# SCH_schematicdesign_2025-10-19.net
KiCad netlist of a schematic drawn in EasyEDA
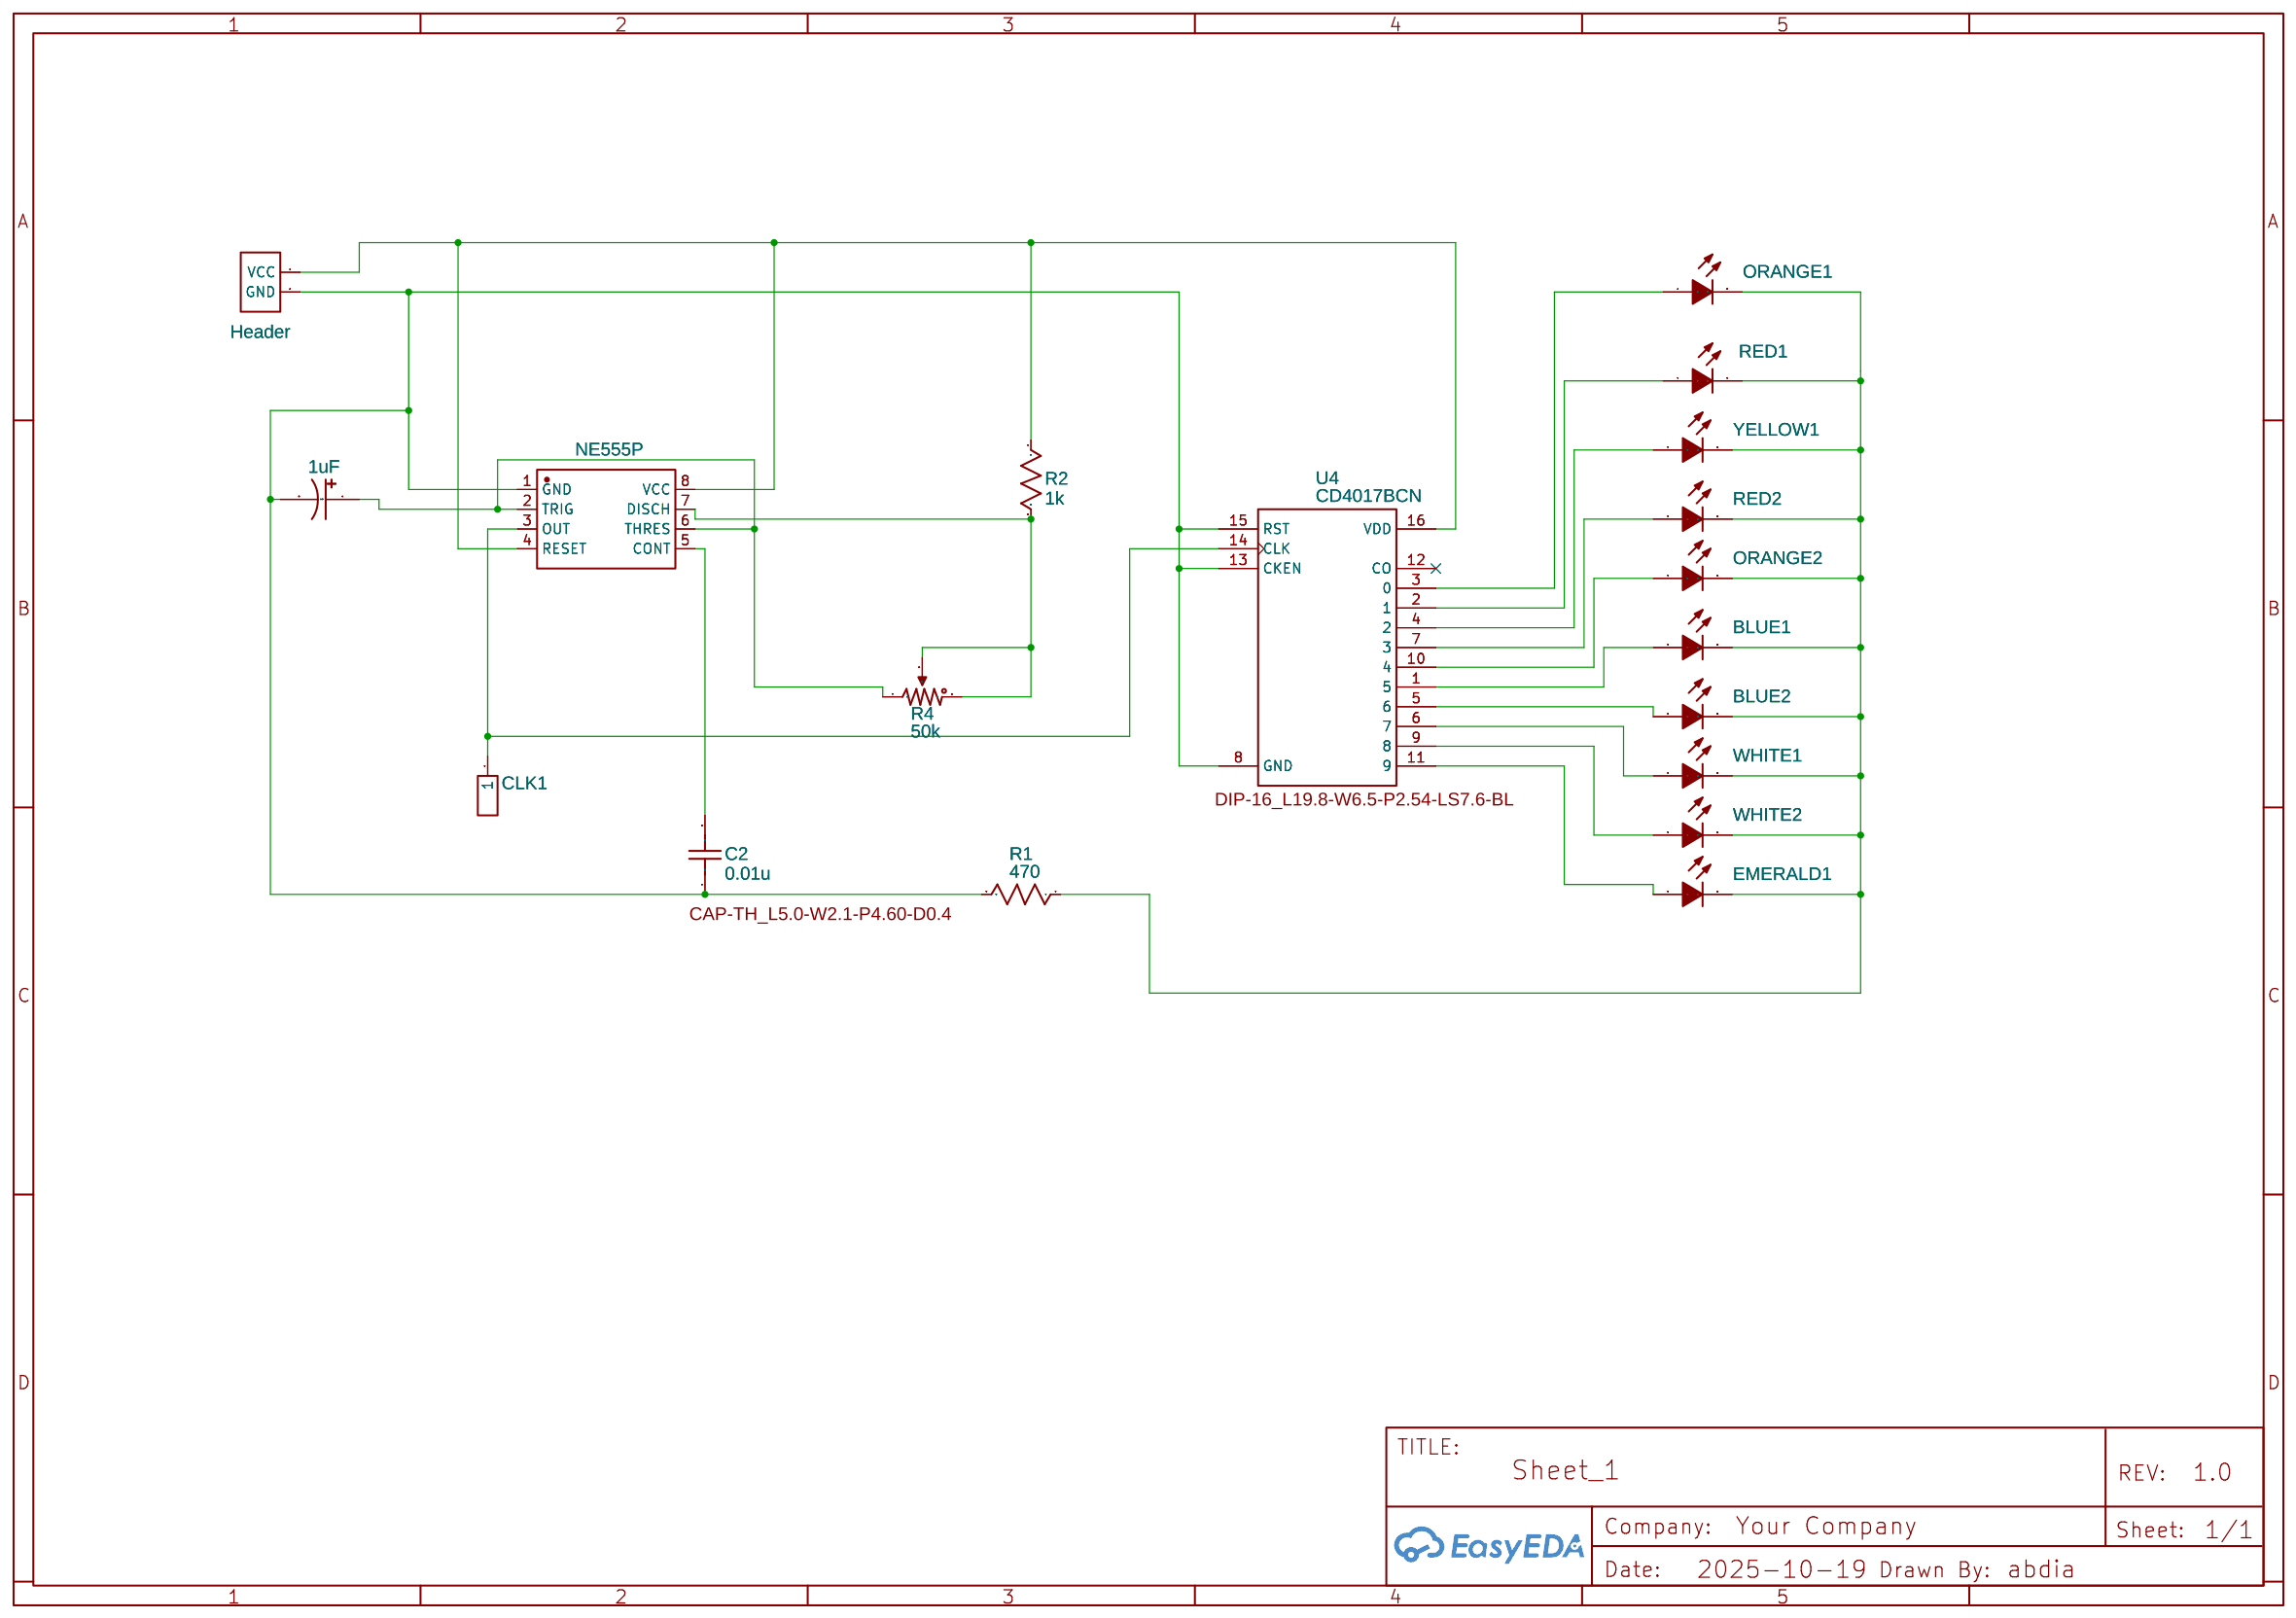
[diagram p0: schematic sheet]

(export (version "E")
  (design (tool "Eeschema 10.0.6"))
  (components
    (comp (ref "BLUE1") (value "LED_5MM") (libsource (lib "") (part "LED_5MM_2")))
    (comp (ref "BLUE2") (value "LED_5MM") (libsource (lib "") (part "LED_5MM_2")))
    (comp (ref "C1")
      (value "1uF")
      (fields (field (name "Manufacturer Part") "UVZ1H010MDD") (field (name "Manufacturer") "Nichicon(尼吉康)"))
      (libsource (lib "") (part "UVZ1H010MDD"))
    )
    (comp (ref "C2") (value "0.01u") (libsource (lib "") (part "C_0603_US")))
    (comp (ref "CLK1")
      (value "C81276")
      (fields
        (field (name "Manufacturer Part") "2.54-1*1P针")
        (field (name "Manufacturer") "BOOMELE(Boom Precision Elec)")
      )
      (libsource (lib "") (part "Header-Male-2.54_1x1"))
    )
    (comp (ref "EMERALD1") (value "LED_5MM") (libsource (lib "") (part "LED_5MM_5")))
    (comp (ref "H1") (value "Header") (libsource (lib "") (part "HEADER-FEMALE-2.54_1X2")))
    (comp (ref "ORANGE1") (value "LED_5MM") (libsource (lib "") (part "LED_5MM_3")))
    (comp (ref "ORANGE2") (value "LED_5MM") (libsource (lib "") (part "LED_5MM_3")))
    (comp (ref "R1")
      (value "470")
      (fields (field (name "Manufacturer Part") "?"))
      (libsource (lib "") (part "Resistor"))
    )
    (comp (ref "R2")
      (value "1k")
      (fields (field (name "Manufacturer Part") "?"))
      (libsource (lib "") (part "Resistor_1"))
    )
    (comp (ref "R4")
      (value "50k")
      (fields (field (name "Manufacturer Part") "?"))
      (libsource (lib "") (part "Potentiometer"))
    )
    (comp (ref "RED1") (value "LED_5MM") (libsource (lib "") (part "LED_5MM_4")))
    (comp (ref "RED2") (value "LED_5MM") (libsource (lib "") (part "LED_5MM_4")))
    (comp (ref "U2")
      (value "NE555P")
      (fields (field (name "Manufacturer") "TI(德州仪器)"))
      (libsource (lib "") (part "NE555P"))
    )
    (comp (ref "U4") (value "CD4017BCN") (libsource (lib "") (part "CD4017BCN")))
    (comp (ref "WHITE1") (value "LED_5MM") (libsource (lib "") (part "LED_5MM")))
    (comp (ref "WHITE2") (value "LED_5MM") (libsource (lib "") (part "LED_5MM")))
    (comp (ref "YELLOW1") (value "LED_5MM") (libsource (lib "") (part "LED_5MM_1")))
  )
  (nets
    (net (code "1") (name "Net-(BLUE1-A)") (class "Default")
      (node (ref "BLUE1") (pin "1") (pinfunction "A_1") (pintype "input"))
      (node (ref "U4") (pin "1") (pinfunction "5_1") (pintype "output"))
    )
    (net (code "2") (name "Net-(BLUE1-K)") (class "Default")
      (node (ref "BLUE1") (pin "2") (pinfunction "K_2") (pintype "input"))
      (node (ref "BLUE2") (pin "2") (pinfunction "K_2") (pintype "input"))
      (node (ref "EMERALD1") (pin "2") (pinfunction "K_2") (pintype "input"))
      (node (ref "ORANGE1") (pin "2") (pinfunction "K_2") (pintype "input"))
      (node (ref "ORANGE2") (pin "2") (pinfunction "K_2") (pintype "input"))
      (node (ref "R1") (pin "1") (pinfunction "1_1") (pintype "unspecified"))
      (node (ref "RED1") (pin "2") (pinfunction "K_2") (pintype "input"))
      (node (ref "RED2") (pin "2") (pinfunction "K_2") (pintype "input"))
      (node (ref "WHITE1") (pin "2") (pinfunction "K_2") (pintype "input"))
      (node (ref "WHITE2") (pin "2") (pinfunction "K_2") (pintype "input"))
      (node (ref "YELLOW1") (pin "2") (pinfunction "K_2") (pintype "input"))
    )
    (net (code "3") (name "Net-(BLUE2-A)") (class "Default")
      (node (ref "BLUE2") (pin "1") (pinfunction "A_1") (pintype "input"))
      (node (ref "U4") (pin "5") (pinfunction "6_5") (pintype "output"))
    )
    (net (code "4") (name "Net-(EMERALD1-A)") (class "Default")
      (node (ref "EMERALD1") (pin "1") (pinfunction "A_1") (pintype "input"))
      (node (ref "U4") (pin "11") (pinfunction "9_11") (pintype "output"))
    )
    (net (code "5") (name "Net-(H1-GND)") (class "Default")
      (node (ref "C1") (pin "2") (pinfunction "2_2") (pintype "unspecified"))
      (node (ref "C2") (pin "1") (pinfunction "1_1") (pintype "unspecified"))
      (node (ref "H1") (pin "2") (pinfunction "GND_2") (pintype "unspecified"))
      (node (ref "R1") (pin "2") (pinfunction "2_2") (pintype "unspecified"))
      (node (ref "U2") (pin "1") (pinfunction "GND_1") (pintype "unspecified"))
      (node (ref "U4") (pin "13") (pinfunction "CKEN_13") (pintype "unspecified"))
      (node (ref "U4") (pin "15") (pinfunction "RST_15") (pintype "unspecified"))
      (node (ref "U4") (pin "8") (pinfunction "GND_8") (pintype "passive"))
    )
    (net (code "6") (name "Net-(H1-VCC)") (class "Default")
      (node (ref "H1") (pin "1") (pinfunction "VCC_1") (pintype "unspecified"))
      (node (ref "R2") (pin "1") (pinfunction "1_1") (pintype "unspecified"))
      (node (ref "U2") (pin "4") (pinfunction "RESET_4") (pintype "unspecified"))
      (node (ref "U2") (pin "8") (pinfunction "VCC_8") (pintype "unspecified"))
      (node (ref "U4") (pin "16") (pinfunction "VDD_16") (pintype "passive"))
    )
    (net (code "7") (name "Net-(ORANGE1-A)") (class "Default")
      (node (ref "ORANGE1") (pin "1") (pinfunction "A_1") (pintype "input"))
      (node (ref "U4") (pin "3") (pinfunction "0_3") (pintype "output"))
    )
    (net (code "8") (name "Net-(ORANGE2-A)") (class "Default")
      (node (ref "ORANGE2") (pin "1") (pinfunction "A_1") (pintype "input"))
      (node (ref "U4") (pin "10") (pinfunction "4_10") (pintype "output"))
    )
    (net (code "9") (name "Net-(R4-2)") (class "Default")
      (node (ref "R2") (pin "2") (pinfunction "2_2") (pintype "unspecified"))
      (node (ref "R4") (pin "2") (pinfunction "3_2") (pintype "unspecified"))
      (node (ref "R4") (pin "3") (pinfunction "2_3") (pintype "unspecified"))
      (node (ref "U2") (pin "7") (pinfunction "DISCH_7") (pintype "unspecified"))
    )
    (net (code "10") (name "Net-(RED1-A)") (class "Default")
      (node (ref "RED1") (pin "1") (pinfunction "A_1") (pintype "input"))
      (node (ref "U4") (pin "2") (pinfunction "1_2") (pintype "output"))
    )
    (net (code "11") (name "Net-(RED2-A)") (class "Default")
      (node (ref "RED2") (pin "1") (pinfunction "A_1") (pintype "input"))
      (node (ref "U4") (pin "7") (pinfunction "3_7") (pintype "output"))
    )
    (net (code "12") (name "Net-(U2-CONT)") (class "Default")
      (node (ref "C2") (pin "2") (pinfunction "2_2") (pintype "unspecified"))
      (node (ref "U2") (pin "5") (pinfunction "CONT_5") (pintype "unspecified"))
    )
    (net (code "13") (name "Net-(U2-OUT)") (class "Default")
      (node (ref "CLK1") (pin "1") (pinfunction "1_1") (pintype "unspecified"))
      (node (ref "U2") (pin "3") (pinfunction "OUT_3") (pintype "unspecified"))
      (node (ref "U4") (pin "14") (pinfunction "CLK_14") (pintype "unspecified"))
    )
    (net (code "14") (name "Net-(U2-THRES)") (class "Default")
      (node (ref "C1") (pin "1") (pinfunction "1_1") (pintype "unspecified"))
      (node (ref "R4") (pin "1") (pinfunction "1_1") (pintype "unspecified"))
      (node (ref "U2") (pin "2") (pinfunction "TRIG_2") (pintype "unspecified"))
      (node (ref "U2") (pin "6") (pinfunction "THRES_6") (pintype "unspecified"))
    )
    (net (code "15") (name "Net-(U4-2)") (class "Default")
      (node (ref "U4") (pin "4") (pinfunction "2_4") (pintype "output"))
      (node (ref "YELLOW1") (pin "1") (pinfunction "A_1") (pintype "input"))
    )
    (net (code "16") (name "Net-(U4-7)") (class "Default")
      (node (ref "U4") (pin "6") (pinfunction "7_6") (pintype "output"))
      (node (ref "WHITE1") (pin "1") (pinfunction "A_1") (pintype "input"))
    )
    (net (code "17") (name "Net-(U4-8)") (class "Default")
      (node (ref "U4") (pin "9") (pinfunction "8_9") (pintype "output"))
      (node (ref "WHITE2") (pin "1") (pinfunction "A_1") (pintype "input"))
    )
    (net (code "18") (name "unconnected-(U4-CO-Pad12)") (class "Default")
      (node (ref "U4") (pin "12") (pinfunction "CO_12") (pintype "output+no_connect"))
    )
  )
)
